# 11_Clock_1.net
KiCad netlist of a schematic drawn in Altium Designer
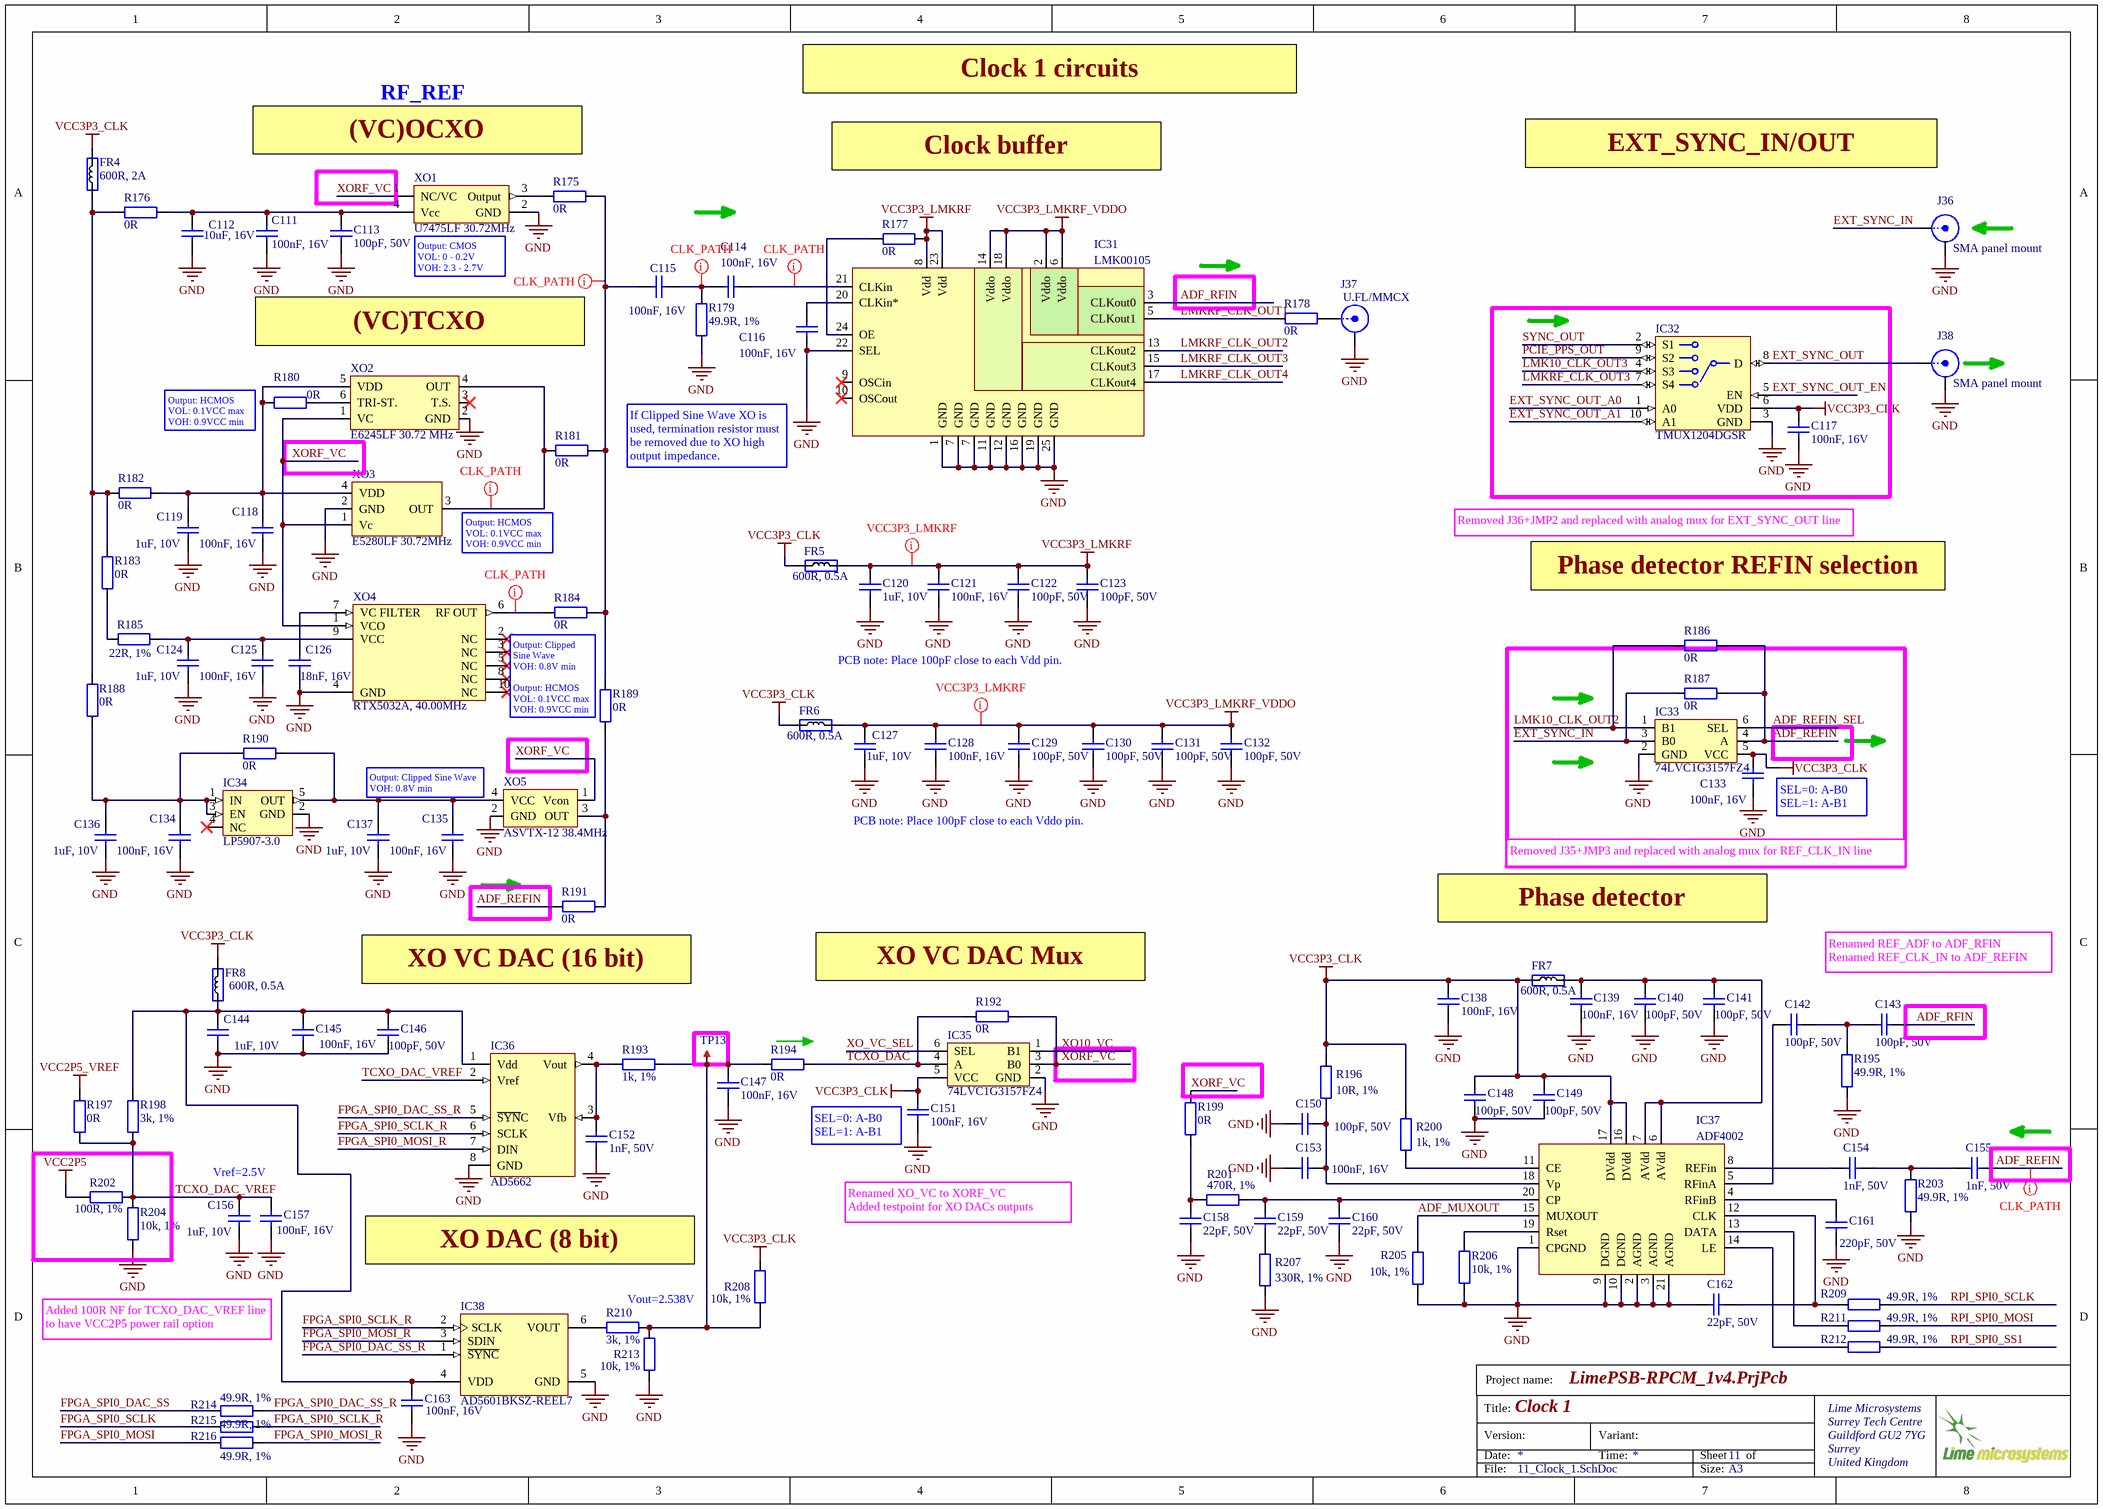
[diagram p0: 11_Clock_1.SchDoc]

(export (version "E")
  (design (tool "Eeschema 10.0.6"))
  (components
    (comp (ref "C111")
      (value "100nF, 16V")
      (footprint "CAP0402")
      (fields
        (field (name "MANUFACTURER") "Murata Electronics")
        (field (name "TOLERANCE") "10 %")
        (field (name "MANUFACTURER PART NUMBER") "GRM155R71C104KA88D")
      )
      (libsource (lib "LimeMicroAltiumLib_schLib") (part "Cap_0402"))
    )
    (comp (ref "C112")
      (value "10uF, 16V")
      (footprint "CAP0603")
      (fields (field (name "MANUFACTURER") "Yageo") (field (name "TOLERANCE") "±20%"))
      (libsource (lib "LimeMicroAltiumLib_schLib") (part "Cap_0603"))
    )
    (comp (ref "C113")
      (value "100pF, 50V")
      (footprint "CAP0402")
      (fields (field (name "TOLERANCE") "±5%") (field (name "MANUFACTURER") "Yageo"))
      (libsource (lib "LimeMicroAltiumLib_schLib") (part "Cap_0402"))
    )
    (comp (ref "C114")
      (value "100nF, 16V")
      (footprint "CAP0402")
      (fields
        (field (name "MANUFACTURER") "Murata Electronics")
        (field (name "TOLERANCE") "10 %")
        (field (name "MANUFACTURER PART NUMBER") "GRM155R71C104KA88D")
      )
      (libsource (lib "LimeMicroAltiumLib_schLib") (part "Cap_0402"))
    )
    (comp (ref "C115")
      (value "100nF, 16V")
      (footprint "CAP0402")
      (fields
        (field (name "MANUFACTURER") "Murata Electronics")
        (field (name "TOLERANCE") "10 %")
        (field (name "MANUFACTURER PART NUMBER") "GRM155R71C104KA88D")
      )
      (libsource (lib "LimeMicroAltiumLib_schLib") (part "Cap_0402"))
    )
    (comp (ref "C116")
      (value "100nF, 16V")
      (footprint "CAP0402")
      (fields
        (field (name "MANUFACTURER") "Murata Electronics")
        (field (name "TOLERANCE") "10 %")
        (field (name "MANUFACTURER PART NUMBER") "GRM155R71C104KA88D")
      )
      (libsource (lib "LimeMicroAltiumLib_schLib") (part "Cap_0402"))
    )
    (comp (ref "C117")
      (value "100nF, 16V")
      (footprint "CAP0402")
      (fields
        (field (name "MANUFACTURER") "Murata Electronics")
        (field (name "TOLERANCE") "10 %")
        (field (name "MANUFACTURER PART NUMBER") "GRM155R71C104KA88D")
      )
      (libsource (lib "LimeMicroAltiumLib_schLib") (part "Cap_0402"))
    )
    (comp (ref "C118")
      (value "100nF, 16V")
      (footprint "CAP0402")
      (fields
        (field (name "MANUFACTURER") "Murata Electronics")
        (field (name "TOLERANCE") "10 %")
        (field (name "MANUFACTURER PART NUMBER") "GRM155R71C104KA88D")
      )
      (libsource (lib "LimeMicroAltiumLib_schLib") (part "Cap_0402"))
    )
    (comp (ref "C119")
      (value "1uF, 10V")
      (footprint "CAP0402")
      (description "CAP CER 1UF 10V X5R 0402")
      (fields (field (name "MANUFACTURER") "Yageo"))
      (libsource (lib "LimeMicroAltiumLib_schLib") (part "Cap_0402"))
    )
    (comp (ref "C120")
      (value "1uF, 10V")
      (footprint "CAP0402")
      (description "CAP CER 1UF 10V X5R 0402")
      (fields (field (name "MANUFACTURER") "Yageo") (field (name "TOLERANCE") "±20%"))
      (libsource (lib "LimeMicroAltiumLib_schLib") (part "Cap_0402"))
    )
    (comp (ref "C121")
      (value "100nF, 16V")
      (footprint "CAP0402")
      (fields
        (field (name "MANUFACTURER") "Murata Electronics")
        (field (name "TOLERANCE") "10 %")
        (field (name "MANUFACTURER PART NUMBER") "GRM155R71C104KA88D")
      )
      (libsource (lib "LimeMicroAltiumLib_schLib") (part "Cap_0402"))
    )
    (comp (ref "C122")
      (value "100pF, 50V")
      (footprint "CAP0402")
      (fields (field (name "MANUFACTURER") "Yageo") (field (name "TOLERANCE") "±5%"))
      (libsource (lib "LimeMicroAltiumLib_schLib") (part "Cap_0402"))
    )
    (comp (ref "C123")
      (value "100pF, 50V")
      (footprint "CAP0402")
      (fields (field (name "MANUFACTURER") "Yageo") (field (name "TOLERANCE") "±5%"))
      (libsource (lib "LimeMicroAltiumLib_schLib") (part "Cap_0402"))
    )
    (comp (ref "C124")
      (value "1uF, 10V")
      (footprint "CAP0402")
      (description "CAP CER 1UF 10V X5R 0402")
      (fields (field (name "MANUFACTURER") "Yageo"))
      (libsource (lib "LimeMicroAltiumLib_schLib") (part "Cap_0402"))
    )
    (comp (ref "C125")
      (value "100nF, 16V")
      (footprint "CAP0402")
      (fields
        (field (name "MANUFACTURER") "Murata Electronics")
        (field (name "TOLERANCE") "10 %")
        (field (name "MANUFACTURER PART NUMBER") "GRM155R71C104KA88D")
      )
      (libsource (lib "LimeMicroAltiumLib_schLib") (part "Cap_0402"))
    )
    (comp (ref "C126")
      (value "18nF, 16V")
      (footprint "CAP0402")
      (fields (field (name "MANUFACTURER") "Yageo") (field (name "TOLERANCE") "±10%"))
      (libsource (lib "LimeMicroAltiumLib_schLib") (part "Cap_0402"))
    )
    (comp (ref "C127")
      (value "1uF, 10V")
      (footprint "CAP0402")
      (description "CAP CER 1UF 10V X5R 0402")
      (fields (field (name "MANUFACTURER") "Yageo") (field (name "TOLERANCE") "±20%"))
      (libsource (lib "LimeMicroAltiumLib_schLib") (part "Cap_0402"))
    )
    (comp (ref "C128")
      (value "100nF, 16V")
      (footprint "CAP0402")
      (fields
        (field (name "MANUFACTURER") "Murata Electronics")
        (field (name "TOLERANCE") "10 %")
        (field (name "MANUFACTURER PART NUMBER") "GRM155R71C104KA88D")
      )
      (libsource (lib "LimeMicroAltiumLib_schLib") (part "Cap_0402"))
    )
    (comp (ref "C129")
      (value "100pF, 50V")
      (footprint "CAP0402")
      (fields (field (name "MANUFACTURER") "Yageo") (field (name "TOLERANCE") "±5%"))
      (libsource (lib "LimeMicroAltiumLib_schLib") (part "Cap_0402"))
    )
    (comp (ref "C130")
      (value "100pF, 50V")
      (footprint "CAP0402")
      (fields (field (name "MANUFACTURER") "Yageo") (field (name "TOLERANCE") "±5%"))
      (libsource (lib "LimeMicroAltiumLib_schLib") (part "Cap_0402"))
    )
    (comp (ref "C131")
      (value "100pF, 50V")
      (footprint "CAP0402")
      (fields (field (name "MANUFACTURER") "Yageo") (field (name "TOLERANCE") "±5%"))
      (libsource (lib "LimeMicroAltiumLib_schLib") (part "Cap_0402"))
    )
    (comp (ref "C132")
      (value "100pF, 50V")
      (footprint "CAP0402")
      (fields (field (name "MANUFACTURER") "Yageo") (field (name "TOLERANCE") "±5%"))
      (libsource (lib "LimeMicroAltiumLib_schLib") (part "Cap_0402"))
    )
    (comp (ref "C133")
      (value "100nF, 16V")
      (footprint "CAP0402")
      (fields
        (field (name "MANUFACTURER") "Murata Electronics")
        (field (name "TOLERANCE") "10 %")
        (field (name "MANUFACTURER PART NUMBER") "GRM155R71C104KA88D")
      )
      (libsource (lib "LimeMicroAltiumLib_schLib") (part "Cap_0402"))
    )
    (comp (ref "C134")
      (value "100nF, 16V")
      (footprint "CAP0402")
      (fields
        (field (name "MANUFACTURER") "Murata Electronics")
        (field (name "TOLERANCE") "10 %")
        (field (name "MANUFACTURER PART NUMBER") "GRM155R71C104KA88D")
      )
      (libsource (lib "") (part "Cap_0402_1"))
    )
    (comp (ref "C135")
      (value "100nF, 16V")
      (footprint "CAP0402")
      (fields
        (field (name "MANUFACTURER") "Murata Electronics")
        (field (name "TOLERANCE") "10 %")
        (field (name "MANUFACTURER PART NUMBER") "GRM155R71C104KA88D")
      )
      (libsource (lib "") (part "Cap_0402_1"))
    )
    (comp (ref "C136")
      (value "1uF, 10V")
      (footprint "CAP0402")
      (fields (field (name "MANUFACTURER") "Yageo"))
      (libsource (lib "") (part "Cap_0402_1"))
    )
    (comp (ref "C137")
      (value "1uF, 10V")
      (footprint "CAP0402")
      (fields (field (name "MANUFACTURER") "Yageo"))
      (libsource (lib "") (part "Cap_0402_1"))
    )
    (comp (ref "C138")
      (value "100nF, 16V")
      (footprint "CAP0402")
      (fields
        (field (name "MANUFACTURER") "Murata Electronics")
        (field (name "TOLERANCE") "10 %")
        (field (name "MANUFACTURER PART NUMBER") "GRM155R71C104KA88D")
      )
      (libsource (lib "LimeMicroAltiumLib_schLib") (part "Cap_0402"))
    )
    (comp (ref "C139")
      (value "100nF, 16V")
      (footprint "CAP0402")
      (fields
        (field (name "MANUFACTURER") "Murata Electronics")
        (field (name "TOLERANCE") "10 %")
        (field (name "MANUFACTURER PART NUMBER") "GRM155R71C104KA88D")
      )
      (libsource (lib "LimeMicroAltiumLib_schLib") (part "Cap_0402"))
    )
    (comp (ref "C140")
      (value "100pF, 50V")
      (footprint "CAP0402")
      (fields (field (name "MANUFACTURER") "Yageo") (field (name "TOLERANCE") "±5%"))
      (libsource (lib "LimeMicroAltiumLib_schLib") (part "Cap_0402"))
    )
    (comp (ref "C141")
      (value "100pF, 50V")
      (footprint "CAP0402")
      (fields (field (name "MANUFACTURER") "Yageo") (field (name "TOLERANCE") "±5%"))
      (libsource (lib "LimeMicroAltiumLib_schLib") (part "Cap_0402"))
    )
    (comp (ref "C142")
      (value "100pF, 50V")
      (footprint "CAP0402")
      (fields (field (name "MANUFACTURER") "Yageo") (field (name "TOLERANCE") "±5%"))
      (libsource (lib "LimeMicroAltiumLib_schLib") (part "Cap_0402"))
    )
    (comp (ref "C143")
      (value "100pF, 50V")
      (footprint "CAP0402")
      (fields (field (name "MANUFACTURER") "Yageo") (field (name "TOLERANCE") "±5%"))
      (libsource (lib "LimeMicroAltiumLib_schLib") (part "Cap_0402"))
    )
    (comp (ref "C144")
      (value "1uF, 10V")
      (footprint "CAP0402")
      (description "CAP CER 1UF 10V X5R 0402")
      (fields (field (name "MANUFACTURER") "Yageo") (field (name "TOLERANCE") "±20%"))
      (libsource (lib "LimeMicroAltiumLib_schLib") (part "Cap_0402"))
    )
    (comp (ref "C145")
      (value "100nF, 16V")
      (footprint "CAP0402")
      (fields
        (field (name "TOLERANCE") "10 %")
        (field (name "MANUFACTURER") "Murata Electronics")
        (field (name "MANUFACTURER PART NUMBER") "GRM155R71C104KA88D")
      )
      (libsource (lib "LimeFPGAboard_schLib") (part "Cap_0603"))
    )
    (comp (ref "C146")
      (value "100pF, 50V")
      (footprint "CAP0402")
      (fields (field (name "MANUFACTURER") "Yageo") (field (name "TOLERANCE") "±5%"))
      (libsource (lib "LimeMicroAltiumLib_schLib") (part "Cap_0402"))
    )
    (comp (ref "C147")
      (value "100nF, 16V")
      (footprint "CAP0402")
      (fields
        (field (name "MANUFACTURER") "Murata Electronics")
        (field (name "TOLERANCE") "10 %")
        (field (name "MANUFACTURER PART NUMBER") "GRM155R71C104KA88D")
      )
      (libsource (lib "LimeMicroAltiumLib_schLib") (part "Cap_0402"))
    )
    (comp (ref "C148")
      (value "100pF, 50V")
      (footprint "CAP0402")
      (fields (field (name "MANUFACTURER") "Yageo") (field (name "TOLERANCE") "±5%"))
      (libsource (lib "LimeMicroAltiumLib_schLib") (part "Cap_0402"))
    )
    (comp (ref "C149")
      (value "100pF, 50V")
      (footprint "CAP0402")
      (fields (field (name "MANUFACTURER") "Yageo") (field (name "TOLERANCE") "±5%"))
      (libsource (lib "LimeMicroAltiumLib_schLib") (part "Cap_0402"))
    )
    (comp (ref "C150")
      (value "100pF, 50V")
      (footprint "CAP0402")
      (fields (field (name "MANUFACTURER") "Yageo") (field (name "TOLERANCE") "±5%"))
      (libsource (lib "LimeMicroAltiumLib_schLib") (part "Cap_0402"))
    )
    (comp (ref "C151")
      (value "100nF, 16V")
      (footprint "CAP0402")
      (fields
        (field (name "MANUFACTURER") "Murata Electronics")
        (field (name "TOLERANCE") "10 %")
        (field (name "MANUFACTURER PART NUMBER") "GRM155R71C104KA88D")
      )
      (libsource (lib "LimeMicroAltiumLib_schLib") (part "Cap_0402"))
    )
    (comp (ref "C152")
      (value "1nF, 50V")
      (footprint "CAP0402")
      (fields
        (field (name "TOLERANCE") "±10%")
        (field (name "MANUFACTURER") "Murata Electronics North America")
      )
      (libsource (lib "LimeMicroAltiumLib_schLib") (part "Cap_0402"))
    )
    (comp (ref "C153")
      (value "100nF, 16V")
      (footprint "CAP0402")
      (fields
        (field (name "MANUFACTURER") "Murata Electronics")
        (field (name "TOLERANCE") "10 %")
        (field (name "MANUFACTURER PART NUMBER") "GRM155R71C104KA88D")
      )
      (libsource (lib "LimeMicroAltiumLib_schLib") (part "Cap_0402"))
    )
    (comp (ref "C154")
      (value "1nF, 50V")
      (footprint "CAP0402")
      (fields
        (field (name "TOLERANCE") "±10%")
        (field (name "MANUFACTURER") "Murata Electronics North America")
      )
      (libsource (lib "LimeMicroAltiumLib_schLib") (part "Cap_0402"))
    )
    (comp (ref "C155")
      (value "1nF, 50V")
      (footprint "CAP0402")
      (fields
        (field (name "TOLERANCE") "±10%")
        (field (name "MANUFACTURER") "Murata Electronics North America")
      )
      (libsource (lib "LimeMicroAltiumLib_schLib") (part "Cap_0402"))
    )
    (comp (ref "C156")
      (value "1uF, 10V")
      (footprint "CAP0402")
      (description "CAP CER 1UF 10V X5R 0402")
      (fields (field (name "MANUFACTURER") "Yageo") (field (name "TOLERANCE") "±20%"))
      (libsource (lib "LimeMicroAltiumLib_schLib") (part "Cap_0402"))
    )
    (comp (ref "C157")
      (value "100nF, 16V")
      (footprint "CAP0402")
      (fields
        (field (name "TOLERANCE") "10 %")
        (field (name "MANUFACTURER") "Murata Electronics")
        (field (name "MANUFACTURER PART NUMBER") "GRM155R71C104KA88D")
      )
      (libsource (lib "LimeFPGAboard_schLib") (part "Cap_0603"))
    )
    (comp (ref "C158")
      (value "22pF, 50V")
      (footprint "CAP0402")
      (fields (field (name "TOLERANCE") "±5%") (field (name "MANUFACTURER") "Yageo"))
      (libsource (lib "LimeMicroAltiumLib_schLib") (part "Cap_0402"))
    )
    (comp (ref "C159")
      (value "22pF, 50V")
      (footprint "CAP0402")
      (fields (field (name "TOLERANCE") "±5%") (field (name "MANUFACTURER") "Yageo"))
      (libsource (lib "LimeMicroAltiumLib_schLib") (part "Cap_0402"))
    )
    (comp (ref "C160")
      (value "22pF, 50V")
      (footprint "CAP0402")
      (fields (field (name "TOLERANCE") "±5%") (field (name "MANUFACTURER") "Yageo"))
      (libsource (lib "LimeMicroAltiumLib_schLib") (part "Cap_0402"))
    )
    (comp (ref "C161")
      (value "220pF, 50V")
      (footprint "CAP0402")
      (fields (field (name "MANUFACTURER") "Yageo") (field (name "TOLERANCE") "±10%"))
      (libsource (lib "LimeMicroAltiumLib_schLib") (part "Cap_0402"))
    )
    (comp (ref "C162")
      (value "22pF, 50V")
      (footprint "CAP0402")
      (fields (field (name "TOLERANCE") "±5%") (field (name "MANUFACTURER") "Yageo"))
      (libsource (lib "LimeMicroAltiumLib_schLib") (part "Cap_0402"))
    )
    (comp (ref "C163")
      (value "100nF, 16V")
      (footprint "CAP0402")
      (fields
        (field (name "TOLERANCE") "10 %")
        (field (name "MANUFACTURER") "Murata Electronics")
        (field (name "MANUFACTURER PART NUMBER") "GRM155R71C104KA88D")
      )
      (libsource (lib "LimeFPGAboard_schLib") (part "Cap_0603"))
    )
    (comp (ref "FR4")
      (value "600R, 2A")
      (footprint "RES0805")
      (fields (field (name "MANUFACTURER") "TDK Corporation"))
      (libsource (lib "LimeFPGAboard_schLib") (part "Ferrite"))
    )
    (comp (ref "FR5")
      (value "600R, 0.5A")
      (footprint "RES0402")
      (fields (field (name "MANUFACTURER") "Murata") (field (name "TOLERANCE") "25%"))
      (libsource (lib "LimeMicroAltiumLib_schLib") (part "Ferrite"))
    )
    (comp (ref "FR6")
      (value "600R, 0.5A")
      (footprint "RES0402")
      (fields (field (name "MANUFACTURER") "Murata") (field (name "TOLERANCE") "25%"))
      (libsource (lib "LimeMicroAltiumLib_schLib") (part "Ferrite"))
    )
    (comp (ref "FR7")
      (value "600R, 0.5A")
      (footprint "RES0402")
      (fields (field (name "MANUFACTURER") "Murata") (field (name "TOLERANCE") "25%"))
      (libsource (lib "LimeMicroAltiumLib_schLib") (part "Ferrite"))
    )
    (comp (ref "FR8")
      (value "600R, 0.5A")
      (footprint "RES0402")
      (fields (field (name "MANUFACTURER") "Murata") (field (name "TOLERANCE") "25%"))
      (libsource (lib "LimeMicroAltiumLib_schLib") (part "Ferrite"))
    )
    (comp (ref "IC31")
      (value "LMK00105")
      (footprint "LMK00105SQ")
      (fields (field (name "MANUFACTURER") "Texas Instruments"))
      (libsource (lib "LimeMicroAltiumLib_schLib") (part "LMK00105"))
    )
    (comp (ref "IC32")
      (value "TMUX1204DGSR")
      (footprint "TMUX1204DGSR_ANALOG_SWITCH_10-TSSOP")
      (fields (field (name "MANUFACTURER") "Texas Instruments"))
      (libsource (lib "LimeMicroAltiumLib") (part "TMUX1204DGSR_ANALOG_SWITCH"))
    )
    (comp (ref "IC33")
      (value "74LVC1G3157FZ4")
      (footprint "74LVC1G3157FZ4_SPDT_SW_DFN1410-6")
      (fields (field (name "MANUFACTURER") "Diodes"))
      (libsource (lib "") (part "74LVC1G3157FZ4_SPDT_SW_1"))
    )
    (comp (ref "IC34")
      (value "LP5907-3.0")
      (footprint "SOT23-5")
      (fields (field (name "MANUFACTURER") "Texas Instruments"))
      (libsource (lib "LimeMicroAltiumLib_schLib_r01") (part "LP5907"))
    )
    (comp (ref "IC35")
      (value "74LVC1G3157FZ4")
      (footprint "74LVC1G3157FZ4_SPDT_SW_DFN1410-6")
      (fields (field (name "MANUFACTURER") "Diodes"))
      (libsource (lib "LimeMicroAltiumLib_schLib_r04") (part "74LVC1G3157FZ4_SPDT_SW"))
    )
    (comp (ref "IC36")
      (value "AD5662")
      (footprint "AD5662_SOT23-8")
      (fields (field (name "MANUFACTURER") "Analog Devices Inc."))
      (libsource (lib "LimeMicroAltiumLib_schLib") (part "AD5662"))
    )
    (comp (ref "IC37")
      (value "ADF4002")
      (footprint "ADF4002")
      (fields (field (name "MANUFACTURER") "Analog Devices Inc"))
      (libsource (lib "LimeMicroAltiumLib_schLib") (part "ADF4002"))
    )
    (comp (ref "IC38")
      (value "AD5601BKSZ-REEL7")
      (footprint "AD5601_SOT23-6")
      (fields (field (name "GENERIC PART NUMBER") "AD5601") (field (name "MANUFACTURER") "Analog Devices"))
      (libsource (lib "LimeMicroAltiumLib_schLib") (part "AD5601BKSZ-REEL7"))
    )
    (comp (ref "J36")
      (value "SMA panel mount")
      (footprint "SMA_connector_side")
      (description "CONN SMA JACK STR 50OHM EDGE MNT")
      (fields (field (name "MANUFACTURER") "Linx"))
      (libsource (lib "") (part "RF_IF_connector_1"))
    )
    (comp (ref "J37")
      (value "U.FL/MMCX")
      (footprint "MMCX_UFL_conn_u")
      (description "CONN UMC RCPT STR 50 OHM SMD")
      (fields (field (name "MANUFACTURER") "Molex, LLC"))
      (libsource (lib "LimeMicroAltiumLib_schLib") (part "RF_IF_connector"))
    )
    (comp (ref "J38")
      (value "SMA panel mount")
      (footprint "SMA_connector_side")
      (description "CONN SMA JACK STR 50OHM EDGE MNT")
      (fields (field (name "MANUFACTURER") "Linx"))
      (libsource (lib "") (part "RF_IF_connector_1"))
    )
    (comp (ref "R175")
      (value "0R")
      (footprint "RES0402_v2")
      (fields (field (name "MANUFACTURER") "Yageo") (field (name "TOLERANCE") "Jumper"))
      (libsource (lib "LimeMicroAltiumLib_schLib") (part "Res_0402"))
    )
    (comp (ref "R176")
      (value "0R")
      (footprint "RES0402")
      (fields (field (name "MANUFACTURER") "Yageo") (field (name "TOLERANCE") "Jumper"))
      (libsource (lib "LimeMicroAltiumLib_schLib") (part "Res_0402"))
    )
    (comp (ref "R177")
      (value "0R")
      (footprint "RES0402")
      (fields (field (name "MANUFACTURER") "Yageo") (field (name "TOLERANCE") "Jumper"))
      (libsource (lib "LimeMicroAltiumLib_schLib") (part "Res_0402"))
    )
    (comp (ref "R178")
      (value "0R")
      (footprint "RES0402")
      (fields (field (name "MANUFACTURER") "Yageo") (field (name "TOLERANCE") "Jumper"))
      (libsource (lib "") (part "Res_0402_1"))
    )
    (comp (ref "R179")
      (value "49.9R, 1%")
      (footprint "RES0402")
      (fields
        (field (name "TOLERANCE") "±1%")
        (field (name "MANUFACTURER") "Samsung Electro-Mechanics America, Inc.")
      )
      (libsource (lib "LimeMicroAltiumLib_schLib") (part "Res_0402"))
    )
    (comp (ref "R180")
      (value "0R")
      (footprint "RES0402")
      (fields (field (name "MANUFACTURER") "Yageo") (field (name "TOLERANCE") "Jumper"))
      (libsource (lib "LimeMicroAltiumLib_schLib") (part "Res_0402"))
    )
    (comp (ref "R181")
      (value "0R")
      (footprint "RES0402_v2")
      (fields (field (name "MANUFACTURER") "Yageo") (field (name "TOLERANCE") "Jumper"))
      (libsource (lib "LimeMicroAltiumLib_schLib") (part "Res_0402"))
    )
    (comp (ref "R182")
      (value "0R")
      (footprint "RES0402")
      (fields (field (name "MANUFACTURER") "Yageo") (field (name "TOLERANCE") "Jumper"))
      (libsource (lib "LimeMicroAltiumLib_schLib") (part "Res_0402"))
    )
    (comp (ref "R183")
      (value "0R")
      (footprint "RES0402")
      (fields (field (name "MANUFACTURER") "Yageo") (field (name "TOLERANCE") "Jumper"))
      (libsource (lib "LimeMicroAltiumLib_schLib") (part "Res_0402"))
    )
    (comp (ref "R184")
      (value "0R")
      (footprint "RES0402_v2")
      (fields (field (name "MANUFACTURER") "Yageo") (field (name "TOLERANCE") "Jumper"))
      (libsource (lib "LimeMicroAltiumLib_schLib") (part "Res_0402"))
    )
    (comp (ref "R185")
      (value "22R, 1%")
      (footprint "RES0402")
      (fields (field (name "TOLERANCE") "±1%") (field (name "MANUFACTURER") "Yageo"))
      (libsource (lib "LimeFPGAboard_schLib") (part "Res_0402"))
    )
    (comp (ref "R186")
      (value "0R")
      (footprint "RES0402_v2")
      (fields (field (name "MANUFACTURER") "Yageo") (field (name "TOLERANCE") "Jumper"))
      (libsource (lib "LimeMicroAltiumLib_schLib") (part "Res_0402"))
    )
    (comp (ref "R187")
      (value "0R")
      (footprint "RES0402_v2")
      (fields (field (name "MANUFACTURER") "Yageo") (field (name "TOLERANCE") "Jumper"))
      (libsource (lib "LimeMicroAltiumLib_schLib") (part "Res_0402"))
    )
    (comp (ref "R188")
      (value "0R")
      (footprint "RES0402")
      (fields (field (name "MANUFACTURER") "Yageo") (field (name "TOLERANCE") "Jumper"))
      (libsource (lib "") (part "Res_0402_1"))
    )
    (comp (ref "R189")
      (value "0R")
      (footprint "RES0402_v2")
      (fields (field (name "MANUFACTURER") "Yageo") (field (name "TOLERANCE") "Jumper"))
      (libsource (lib "") (part "Res_0402_1"))
    )
    (comp (ref "R190")
      (value "0R")
      (footprint "RES0402")
      (fields (field (name "MANUFACTURER") "Yageo") (field (name "TOLERANCE") "Jumper"))
      (libsource (lib "") (part "Res_0402_1"))
    )
    (comp (ref "R191")
      (value "0R")
      (footprint "RES0402_v2")
      (fields (field (name "MANUFACTURER") "Yageo") (field (name "TOLERANCE") "Jumper"))
      (libsource (lib "LimeMicroAltiumLib_schLib") (part "Res_0402"))
    )
    (comp (ref "R192")
      (value "0R")
      (footprint "RES0402_v2")
      (fields (field (name "MANUFACTURER") "Yageo") (field (name "TOLERANCE") "Jumper"))
      (libsource (lib "LimeMicroAltiumLib_schLib") (part "Res_0402"))
    )
    (comp (ref "R193")
      (value "1k, 1%")
      (footprint "RES0402")
      (fields (field (name "MANUFACTURER") "Stackpole Electronics Inc") (field (name "TOLERANCE") "±1%"))
      (libsource (lib "LimeMicroAltiumLib_schLib") (part "Res_0402"))
    )
    (comp (ref "R194")
      (value "0R")
      (footprint "RES0402")
      (fields (field (name "MANUFACTURER") "Yageo") (field (name "TOLERANCE") "Jumper"))
      (libsource (lib "LimeMicroAltiumLib_schLib") (part "Res_0402"))
    )
    (comp (ref "R195")
      (value "49.9R, 1%")
      (footprint "RES0402")
      (fields
        (field (name "TOLERANCE") "±1%")
        (field (name "MANUFACTURER") "Samsung Electro-Mechanics America, Inc.")
      )
      (libsource (lib "LimeMicroAltiumLib_schLib") (part "Res_0402"))
    )
    (comp (ref "R196")
      (value "10R, 1%")
      (footprint "RES0402")
      (fields (field (name "MANUFACTURER") "Stackpole Electronics") (field (name "TOLERANCE") "1%"))
      (libsource (lib "LimeMicroAltiumLib_schLib") (part "Res_0402"))
    )
    (comp (ref "R197")
      (value "0R")
      (footprint "RES0402_v2")
      (fields (field (name "MANUFACTURER") "Yageo") (field (name "TOLERANCE") "Jumper"))
      (libsource (lib "LimeMicroAltiumLib_schLib") (part "Res_0402"))
    )
    (comp (ref "R198")
      (value "3k, 1%")
      (footprint "RES0402")
      (fields (field (name "TOLERANCE") "±1%") (field (name "MANUFACTURER") "Vishay Dale"))
      (libsource (lib "LimeMicroAltiumLib_schLib") (part "Res_0402"))
    )
    (comp (ref "R199")
      (value "0R")
      (footprint "RES0402")
      (fields (field (name "MANUFACTURER") "Yageo") (field (name "TOLERANCE") "Jumper"))
      (libsource (lib "LimeMicroAltiumLib_schLib") (part "Res_0402"))
    )
    (comp (ref "R200")
      (value "1k, 1%")
      (footprint "RES0402")
      (fields (field (name "MANUFACTURER") "Stackpole Electronics Inc") (field (name "TOLERANCE") "±1%"))
      (libsource (lib "LimeMicroAltiumLib_schLib") (part "Res_0402"))
    )
    (comp (ref "R201")
      (value "470R, 1%")
      (footprint "RES0402")
      (fields (field (name "TOLERANCE") "1%") (field (name "MANUFACTURER") "Yageo"))
      (libsource (lib "") (part "Res_0402_1"))
    )
    (comp (ref "R202")
      (value "100R, 1%")
      (footprint "RES0402")
      (fields (field (name "TOLERANCE") "±1%") (field (name "MANUFACTURER") "Stackpole Electronics Inc."))
      (libsource (lib "LimeMicroAltiumLib_schLib") (part "Res_0402"))
    )
    (comp (ref "R203")
      (value "49.9R, 1%")
      (footprint "RES0402")
      (fields
        (field (name "TOLERANCE") "±1%")
        (field (name "MANUFACTURER") "Samsung Electro-Mechanics America, Inc.")
      )
      (libsource (lib "LimeMicroAltiumLib_schLib") (part "Res_0402"))
    )
    (comp (ref "R204")
      (value "10k, 1%")
      (footprint "RES0402")
      (fields (field (name "MANUFACTURER") "Yageo") (field (name "TOLERANCE") "±1%"))
      (libsource (lib "LimeMicroAltiumLib_schLib") (part "Res_0402"))
    )
    (comp (ref "R205")
      (value "10k, 1%")
      (footprint "RES0402")
      (fields (field (name "MANUFACTURER") "Yageo") (field (name "TOLERANCE") "±1%"))
      (libsource (lib "LimeMicroAltiumLib_schLib") (part "Res_0402"))
    )
    (comp (ref "R206")
      (value "10k, 1%")
      (footprint "RES0402")
      (fields (field (name "MANUFACTURER") "Yageo") (field (name "TOLERANCE") "±1%"))
      (libsource (lib "LimeMicroAltiumLib_schLib") (part "Res_0402"))
    )
    (comp (ref "R207")
      (value "330R, 1%")
      (footprint "RES0402")
      (fields (field (name "MANUFACTURER") "Yageo") (field (name "TOLERANCE") "1%"))
      (libsource (lib "LimeMicroAltiumLib_schLib") (part "Res_0402"))
    )
    (comp (ref "R208")
      (value "10k, 1%")
      (footprint "RES0402")
      (fields (field (name "MANUFACTURER") "Yageo") (field (name "TOLERANCE") "±1%"))
      (libsource (lib "LimeMicroAltiumLib_schLib") (part "Res_0402"))
    )
    (comp (ref "R209")
      (value "49.9R, 1%")
      (footprint "RES0402")
      (fields
        (field (name "TOLERANCE") "±1%")
        (field (name "MANUFACTURER") "Samsung Electro-Mechanics America, Inc.")
      )
      (libsource (lib "LimeMicroAltiumLib_schLib") (part "Res_0402"))
    )
    (comp (ref "R210")
      (value "3k, 1%")
      (footprint "RES0402")
      (fields (field (name "TOLERANCE") "±1%") (field (name "MANUFACTURER") "Vishay Dale"))
      (libsource (lib "LimeMicroAltiumLib_schLib") (part "Res_0402"))
    )
    (comp (ref "R211")
      (value "49.9R, 1%")
      (footprint "RES0402")
      (fields
        (field (name "TOLERANCE") "±1%")
        (field (name "MANUFACTURER") "Samsung Electro-Mechanics America, Inc.")
      )
      (libsource (lib "LimeMicroAltiumLib_schLib") (part "Res_0402"))
    )
    (comp (ref "R212")
      (value "49.9R, 1%")
      (footprint "RES0402")
      (fields
        (field (name "TOLERANCE") "±1%")
        (field (name "MANUFACTURER") "Samsung Electro-Mechanics America, Inc.")
      )
      (libsource (lib "LimeMicroAltiumLib_schLib") (part "Res_0402"))
    )
    (comp (ref "R213")
      (value "10k, 1%")
      (footprint "RES0402")
      (fields (field (name "MANUFACTURER") "Yageo") (field (name "TOLERANCE") "±1%"))
      (libsource (lib "LimeMicroAltiumLib_schLib") (part "Res_0402"))
    )
    (comp (ref "R214")
      (value "49.9R, 1%")
      (footprint "RES0402")
      (fields
        (field (name "TOLERANCE") "±1%")
        (field (name "MANUFACTURER") "Samsung Electro-Mechanics America, Inc.")
      )
      (libsource (lib "LimeMicroAltiumLib_schLib") (part "Res_0402"))
    )
    (comp (ref "R215")
      (value "49.9R, 1%")
      (footprint "RES0402")
      (fields
        (field (name "TOLERANCE") "±1%")
        (field (name "MANUFACTURER") "Samsung Electro-Mechanics America, Inc.")
      )
      (libsource (lib "LimeMicroAltiumLib_schLib") (part "Res_0402"))
    )
    (comp (ref "R216")
      (value "49.9R, 1%")
      (footprint "RES0402")
      (fields
        (field (name "TOLERANCE") "±1%")
        (field (name "MANUFACTURER") "Samsung Electro-Mechanics America, Inc.")
      )
      (libsource (lib "LimeMicroAltiumLib_schLib") (part "Res_0402"))
    )
    (comp (ref "TP13")
      (value "TESTPOINT_PAD")
      (footprint "TP_PAD_1p5MM")
      (description "Test Point PCB mount Miniature White")
      (libsource (lib "LimeMicroAltiumLib_schLib_r04") (part "TESTPOINT_PAD"))
    )
    (comp (ref "XO1")
      (value "U7475LF 30.72MHz")
      (footprint "AOCJYR-10.000MHz")
      (fields (field (name "MANUFACTURER") "Rakon"))
      (libsource (lib "LimeMicroAltiumLib_schLib") (part "AOCJYR-10.000MHz"))
    )
    (comp (ref "XO2")
      (value "E6245LF 30.72 MHz")
      (footprint "RAKON_RPT7050A")
      (fields (field (name "MANUFACTURER") "Rakon"))
      (libsource (lib "LimeMicroAltiumLib_schLib") (part "RPT7050A"))
    )
    (comp (ref "XO3")
      (value "E5280LF 30.72MHz")
      (footprint "RAKON_TXCO")
      (fields (field (name "MANUFACTURER") "Rakon"))
      (libsource (lib "LimeMicroAltiumLib_schLib") (part "TXCO"))
    )
    (comp (ref "XO4")
      (value "RTX5032A, 40.00MHz")
      (footprint "RAKON_RTX5032A")
      (fields (field (name "MANUFACTURER") "Rakon"))
      (libsource (lib "LimeMicroAltiumLib_schLib") (part "Rakon_RTX5032A"))
    )
    (comp (ref "XO5")
      (value "ASVTX-12 38.4MHz")
      (footprint "CRYSTAL_4-LCC_2P5x2P0")
      (description "Oscillator Crystal")
      (fields (field (name "MANUFACTURER") "Abracon"))
      (libsource (lib "LimeMicroAltiumLib_schLib_r01") (part "ASVTX-12-A-38.400MHZ-H10-T_CRYSTAL"))
    )
  )
  (nets
    (net (code "2") (name "/ADF_MUXOUT") (class "Default")
      (node (ref "IC37") (pin "15") (pinfunction "MUXOUT_15") (pintype "passive"))
      (node (ref "R205") (pin "1") (pinfunction "1_1") (pintype "passive"))
    )
    (net (code "3") (name "/ADF_REFIN") (class "Default")
      (node (ref "C155") (pin "2") (pinfunction "2_2") (pintype "passive"))
      (node (ref "IC33") (pin "4") (pinfunction "A_4") (pintype "passive"))
      (node (ref "R186") (pin "1") (pinfunction "1_1") (pintype "passive"))
      (node (ref "R187") (pin "1") (pinfunction "1_1") (pintype "passive"))
      (node (ref "R191") (pin "2") (pinfunction "2_2") (pintype "passive"))
    )
    (net (code "4") (name "/ADF_REFIN_SEL") (class "Default")
      (node (ref "IC33") (pin "6") (pinfunction "SEL_6") (pintype "passive"))
    )
    (net (code "5") (name "/ADF_RFIN") (class "Default")
      (node (ref "C143") (pin "2") (pinfunction "2_2") (pintype "passive"))
      (node (ref "IC31") (pin "3") (pinfunction "CLKout0_3") (pintype "passive"))
    )
    (net (code "6") (name "/EXT_SYNC_IN") (class "Default")
      (node (ref "IC33") (pin "3") (pinfunction "B0_3") (pintype "passive"))
      (node (ref "J36") (pin "1") (pinfunction "X_1") (pintype "passive"))
      (node (ref "R187") (pin "2") (pinfunction "2_2") (pintype "passive"))
    )
    (net (code "7") (name "/EXT_SYNC_OUT") (class "Default")
      (node (ref "IC32") (pin "8") (pinfunction "D_8") (pintype "bidirectional"))
      (node (ref "J38") (pin "1") (pinfunction "X_1") (pintype "passive"))
    )
    (net (code "8") (name "/EXT_SYNC_OUT_A0") (class "Default")
      (node (ref "IC32") (pin "1") (pinfunction "A0_1") (pintype "input"))
    )
    (net (code "9") (name "/EXT_SYNC_OUT_A1") (class "Default")
      (node (ref "IC32") (pin "10") (pinfunction "A1_10") (pintype "bidirectional"))
    )
    (net (code "10") (name "/EXT_SYNC_OUT_EN") (class "Default")
      (node (ref "IC32") (pin "5") (pinfunction "EN_5") (pintype "input"))
    )
    (net (code "11") (name "/FPGA_SPI0_DAC_SS") (class "Default")
      (node (ref "R214") (pin "2") (pinfunction "2_2") (pintype "passive"))
    )
    (net (code "12") (name "/FPGA_SPI0_DAC_SS_R") (class "Default")
      (node (ref "IC36") (pin "5") (pinfunction "~{SYN}C_5") (pintype "input"))
      (node (ref "IC38") (pin "1") (pinfunction "~{SYNC}_1") (pintype "input"))
      (node (ref "R214") (pin "1") (pinfunction "1_1") (pintype "passive"))
    )
    (net (code "13") (name "/FPGA_SPI0_MOSI") (class "Default")
      (node (ref "R216") (pin "2") (pinfunction "2_2") (pintype "passive"))
    )
    (net (code "14") (name "/FPGA_SPI0_MOSI_R") (class "Default")
      (node (ref "IC36") (pin "7") (pinfunction "DIN_7") (pintype "input"))
      (node (ref "IC38") (pin "3") (pinfunction "SDIN_3") (pintype "input"))
      (node (ref "R216") (pin "1") (pinfunction "1_1") (pintype "passive"))
    )
    (net (code "15") (name "/FPGA_SPI0_SCLK") (class "Default")
      (node (ref "R215") (pin "2") (pinfunction "2_2") (pintype "passive"))
    )
    (net (code "16") (name "/FPGA_SPI0_SCLK_R") (class "Default")
      (node (ref "IC36") (pin "6") (pinfunction "SCLK_6") (pintype "input"))
      (node (ref "IC38") (pin "2") (pinfunction "SCLK_2") (pintype "input"))
      (node (ref "R215") (pin "1") (pinfunction "1_1") (pintype "passive"))
    )
    (net (code "17") (name "/LMK10_CLK_OUT2") (class "Default")
      (node (ref "IC33") (pin "1") (pinfunction "B1_1") (pintype "passive"))
      (node (ref "R186") (pin "2") (pinfunction "2_2") (pintype "passive"))
    )
    (net (code "18") (name "/LMK10_CLK_OUT3") (class "Default")
      (node (ref "IC32") (pin "4") (pinfunction "S3_4") (pintype "bidirectional"))
    )
    (net (code "19") (name "/LMKRF_CLK_OUT1") (class "Default")
      (node (ref "IC31") (pin "5") (pinfunction "CLKout1_5") (pintype "passive"))
      (node (ref "R178") (pin "2") (pinfunction "2_2") (pintype "passive"))
    )
    (net (code "20") (name "/LMKRF_CLK_OUT2") (class "Default")
      (node (ref "IC31") (pin "13") (pinfunction "CLKout2_13") (pintype "passive"))
    )
    (net (code "21") (name "/LMKRF_CLK_OUT3") (class "Default")
      (node (ref "IC31") (pin "15") (pinfunction "CLKout3_15") (pintype "passive"))
      (node (ref "IC32") (pin "7") (pinfunction "S4_7") (pintype "bidirectional"))
    )
    (net (code "22") (name "/LMKRF_CLK_OUT4") (class "Default")
      (node (ref "IC31") (pin "17") (pinfunction "CLKout4_17") (pintype "passive"))
    )
    (net (code "23") (name "/PCIE_PPS_OUT") (class "Default")
      (node (ref "IC32") (pin "9") (pinfunction "S2_9") (pintype "bidirectional"))
    )
    (net (code "24") (name "/RPI_SPI0_MOSI") (class "Default")
      (node (ref "R211") (pin "1") (pinfunction "1_1") (pintype "passive"))
    )
    (net (code "25") (name "/RPI_SPI0_SCLK") (class "Default")
      (node (ref "R209") (pin "1") (pinfunction "1_1") (pintype "passive"))
    )
    (net (code "26") (name "/RPI_SPI0_SS1") (class "Default")
      (node (ref "R212") (pin "1") (pinfunction "1_1") (pintype "passive"))
    )
    (net (code "27") (name "/SYNC_OUT") (class "Default")
      (node (ref "IC32") (pin "2") (pinfunction "S1_2") (pintype "bidirectional"))
    )
    (net (code "28") (name "/TCXO_DAC") (class "Default")
      (node (ref "IC35") (pin "4") (pinfunction "A_4") (pintype "passive"))
      (node (ref "R192") (pin "2") (pinfunction "2_2") (pintype "passive"))
      (node (ref "R194") (pin "1") (pinfunction "1_1") (pintype "passive"))
    )
    (net (code "29") (name "/TCXO_DAC_VREF") (class "Default")
      (node (ref "C156") (pin "2") (pinfunction "2_2") (pintype "passive"))
      (node (ref "C157") (pin "1") (pinfunction "1_1") (pintype "passive"))
      (node (ref "IC36") (pin "2") (pinfunction "Vref_2") (pintype "input"))
      (node (ref "R197") (pin "1") (pinfunction "1_1") (pintype "passive"))
      (node (ref "R198") (pin "1") (pinfunction "1_1") (pintype "passive"))
      (node (ref "R202") (pin "1") (pinfunction "1_1") (pintype "passive"))
      (node (ref "R204") (pin "1") (pinfunction "1_1") (pintype "passive"))
    )
    (net (code "30") (name "/XO10_VC") (class "Default")
      (node (ref "IC35") (pin "1") (pinfunction "B1_1") (pintype "passive"))
    )
    (net (code "31") (name "/XORF_VC") (class "Default")
      (node (ref "IC35") (pin "3") (pinfunction "B0_3") (pintype "passive"))
      (node (ref "R192") (pin "1") (pinfunction "1_1") (pintype "passive"))
      (node (ref "R199") (pin "2") (pinfunction "2_2") (pintype "passive"))
      (node (ref "XO1") (pin "1") (pinfunction "NC/VC_1") (pintype "passive"))
      (node (ref "XO2") (pin "1") (pinfunction "VC_1") (pintype "passive"))
      (node (ref "XO3") (pin "1") (pinfunction "Vc_1") (pintype "passive"))
      (node (ref "XO4") (pin "1") (pinfunction "VCO_1") (pintype "input"))
      (node (ref "XO5") (pin "1") (pinfunction "Vcon_1") (pintype "passive"))
    )
    (net (code "32") (name "/XO_VC_SEL") (class "Default")
      (node (ref "IC35") (pin "6") (pinfunction "SEL_6") (pintype "passive"))
    )
    (net (code "33") (name "GND") (class "Default")
      (node (ref "C111") (pin "1") (pinfunction "1_1") (pintype "passive"))
      (node (ref "C112") (pin "1") (pinfunction "1_1") (pintype "passive"))
      (node (ref "C113") (pin "2") (pinfunction "2_2") (pintype "passive"))
      (node (ref "C116") (pin "1") (pinfunction "1_1") (pintype "passive"))
      (node (ref "C117") (pin "1") (pinfunction "1_1") (pintype "passive"))
      (node (ref "C118") (pin "1") (pinfunction "1_1") (pintype "passive"))
      (node (ref "C119") (pin "1") (pinfunction "1_1") (pintype "passive"))
      (node (ref "C120") (pin "1") (pinfunction "1_1") (pintype "passive"))
      (node (ref "C121") (pin "1") (pinfunction "1_1") (pintype "passive"))
      (node (ref "C122") (pin "1") (pinfunction "1_1") (pintype "passive"))
      (node (ref "C123") (pin "1") (pinfunction "1_1") (pintype "passive"))
      (node (ref "C124") (pin "1") (pinfunction "1_1") (pintype "passive"))
      (node (ref "C125") (pin "1") (pinfunction "1_1") (pintype "passive"))
      (node (ref "C126") (pin "1") (pinfunction "1_1") (pintype "passive"))
      (node (ref "C127") (pin "1") (pinfunction "1_1") (pintype "passive"))
      (node (ref "C128") (pin "1") (pinfunction "1_1") (pintype "passive"))
      (node (ref "C129") (pin "1") (pinfunction "1_1") (pintype "passive"))
      (node (ref "C130") (pin "1") (pinfunction "1_1") (pintype "passive"))
      (node (ref "C131") (pin "1") (pinfunction "1_1") (pintype "passive"))
      (node (ref "C132") (pin "1") (pinfunction "1_1") (pintype "passive"))
      (node (ref "C133") (pin "1") (pinfunction "1_1") (pintype "passive"))
      (node (ref "C134") (pin "1") (pinfunction "1_1") (pintype "passive"))
      (node (ref "C135") (pin "1") (pinfunction "1_1") (pintype "passive"))
      (node (ref "C136") (pin "1") (pinfunction "1_1") (pintype "passive"))
      (node (ref "C137") (pin "1") (pinfunction "1_1") (pintype "passive"))
      (node (ref "C138") (pin "1") (pinfunction "1_1") (pintype "passive"))
      (node (ref "C139") (pin "1") (pinfunction "1_1") (pintype "passive"))
      (node (ref "C140") (pin "2") (pinfunction "2_2") (pintype "passive"))
      (node (ref "C141") (pin "2") (pinfunction "2_2") (pintype "passive"))
      (node (ref "C144") (pin "1") (pinfunction "1_1") (pintype "passive"))
      (node (ref "C145") (pin "2") (pinfunction "2_2") (pintype "passive"))
      (node (ref "C146") (pin "2") (pinfunction "2_2") (pintype "passive"))
      (node (ref "C147") (pin "1") (pinfunction "1_1") (pintype "passive"))
      (node (ref "C148") (pin "2") (pinfunction "2_2") (pintype "passive"))
      (node (ref "C149") (pin "2") (pinfunction "2_2") (pintype "passive"))
      (node (ref "C150") (pin "1") (pinfunction "1_1") (pintype "passive"))
      (node (ref "C151") (pin "1") (pinfunction "1_1") (pintype "passive"))
      (node (ref "C152") (pin "2") (pinfunction "2_2") (pintype "passive"))
      (node (ref "C153") (pin "2") (pinfunction "2_2") (pintype "passive"))
      (node (ref "C156") (pin "1") (pinfunction "1_1") (pintype "passive"))
      (node (ref "C157") (pin "2") (pinfunction "2_2") (pintype "passive"))
      (node (ref "C158") (pin "1") (pinfunction "1_1") (pintype "passive"))
      (node (ref "C160") (pin "1") (pinfunction "1_1") (pintype "passive"))
      (node (ref "C161") (pin "2") (pinfunction "2_2") (pintype "passive"))
      (node (ref "C162") (pin "2") (pinfunction "2_2") (pintype "passive"))
      (node (ref "C163") (pin "2") (pinfunction "2_2") (pintype "passive"))
      (node (ref "IC31") (pin "1") (pinfunction "GND_1") (pintype "passive"))
      (node (ref "IC31") (pin "11") (pinfunction "GND_11") (pintype "passive"))
      (node (ref "IC31") (pin "12") (pinfunction "GND_12") (pintype "passive"))
      (node (ref "IC31") (pin "16") (pinfunction "GND_16") (pintype "passive"))
      (node (ref "IC31") (pin "19") (pinfunction "GND_19") (pintype "passive"))
      (node (ref "IC31") (pin "22") (pinfunction "SEL_22") (pintype "passive"))
      (node (ref "IC31") (pin "25") (pinfunction "GND_25") (pintype "passive"))
      (node (ref "IC31") (pin "7") (pinfunction "GND_7") (pintype "passive"))
      (node (ref "IC32") (pin "3") (pinfunction "GND_3") (pintype "passive"))
      (node (ref "IC33") (pin "2") (pinfunction "GND_2") (pintype "passive"))
      (node (ref "IC34") (pin "2") (pinfunction "GND_2") (pintype "passive"))
      (node (ref "IC35") (pin "2") (pinfunction "GND_2") (pintype "passive"))
      (node (ref "IC36") (pin "8") (pinfunction "GND_8") (pintype "passive"))
      (node (ref "IC37") (pin "1") (pinfunction "CPGND_1") (pintype "passive"))
      (node (ref "IC37") (pin "10") (pinfunction "DGND_10") (pintype "passive"))
      (node (ref "IC37") (pin "2") (pinfunction "AGND_2") (pintype "passive"))
      (node (ref "IC37") (pin "21") (pinfunction "AGND_21") (pintype "passive"))
      (node (ref "IC37") (pin "3") (pinfunction "AGND_3") (pintype "passive"))
      (node (ref "IC37") (pin "9") (pinfunction "DGND_9") (pintype "passive"))
      (node (ref "IC38") (pin "5") (pinfunction "GND_5") (pintype "power_in"))
      (node (ref "J36") (pin "2") (pinfunction "Y_2") (pintype "passive"))
      (node (ref "J37") (pin "2") (pinfunction "Y_2") (pintype "passive"))
      (node (ref "J38") (pin "2") (pinfunction "Y_2") (pintype "passive"))
      (node (ref "R179") (pin "1") (pinfunction "1_1") (pintype "passive"))
      (node (ref "R195") (pin "1") (pinfunction "1_1") (pintype "passive"))
      (node (ref "R203") (pin "1") (pinfunction "1_1") (pintype "passive"))
      (node (ref "R204") (pin "2") (pinfunction "2_2") (pintype "passive"))
      (node (ref "R205") (pin "2") (pinfunction "2_2") (pintype "passive"))
      (node (ref "R206") (pin "2") (pinfunction "2_2") (pintype "passive"))
      (node (ref "R207") (pin "1") (pinfunction "1_1") (pintype "passive"))
      (node (ref "R213") (pin "2") (pinfunction "2_2") (pintype "passive"))
      (node (ref "XO1") (pin "2") (pinfunction "GND_2") (pintype "passive"))
      (node (ref "XO2") (pin "2") (pinfunction "GND_2") (pintype "passive"))
      (node (ref "XO3") (pin "2") (pinfunction "GND_2") (pintype "passive"))
      (node (ref "XO4") (pin "4") (pinfunction "GND_4") (pintype "passive"))
      (node (ref "XO5") (pin "2") (pinfunction "GND_2") (pintype "passive"))
    )
    (net (code "34") (name "Net-(C114-Pad2)") (class "Default")
      (node (ref "C114") (pin "2") (pinfunction "2_2") (pintype "passive"))
      (node (ref "C115") (pin "1") (pinfunction "1_1") (pintype "passive"))
      (node (ref "R179") (pin "2") (pinfunction "2_2") (pintype "passive"))
    )
    (net (code "35") (name "Net-(C115-Pad2)") (class "Default")
      (node (ref "C115") (pin "2") (pinfunction "2_2") (pintype "passive"))
      (node (ref "R175") (pin "1") (pinfunction "1_1") (pintype "passive"))
      (node (ref "R181") (pin "1") (pinfunction "1_1") (pintype "passive"))
      (node (ref "R184") (pin "2") (pinfunction "2_2") (pintype "passive"))
      (node (ref "R189") (pin "1") (pinfunction "1_1") (pintype "passive"))
    )
    (net (code "36") (name "Net-(C139-Pad2)") (class "Default")
      (node (ref "C139") (pin "2") (pinfunction "2_2") (pintype "passive"))
      (node (ref "C140") (pin "1") (pinfunction "1_1") (pintype "passive"))
      (node (ref "C141") (pin "1") (pinfunction "1_1") (pintype "passive"))
      (node (ref "FR7") (pin "2") (pinfunction "2_2") (pintype "passive"))
      (node (ref "IC37") (pin "6") (pinfunction "AVdd_6") (pintype "passive"))
      (node (ref "IC37") (pin "7") (pinfunction "AVdd_7") (pintype "passive"))
    )
    (net (code "37") (name "Net-(C142-Pad2)") (class "Default")
      (node (ref "C142") (pin "2") (pinfunction "2_2") (pintype "passive"))
      (node (ref "C143") (pin "1") (pinfunction "1_1") (pintype "passive"))
      (node (ref "R195") (pin "2") (pinfunction "2_2") (pintype "passive"))
    )
    (net (code "38") (name "Net-(C147-Pad2)") (class "Default")
      (node (ref "C147") (pin "2") (pinfunction "2_2") (pintype "passive"))
      (node (ref "R193") (pin "1") (pinfunction "1_1") (pintype "passive"))
      (node (ref "R194") (pin "2") (pinfunction "2_2") (pintype "passive"))
      (node (ref "R208") (pin "2") (pinfunction "2_2") (pintype "passive"))
      (node (ref "R210") (pin "1") (pinfunction "1_1") (pintype "passive"))
      (node (ref "R213") (pin "1") (pinfunction "1_1") (pintype "passive"))
      (node (ref "TP13") (pin "1") (pintype "passive"))
    )
    (net (code "39") (name "Net-(C154-Pad2)") (class "Default")
      (node (ref "C154") (pin "2") (pinfunction "2_2") (pintype "passive"))
      (node (ref "C155") (pin "1") (pinfunction "1_1") (pintype "passive"))
      (node (ref "R203") (pin "2") (pinfunction "2_2") (pintype "passive"))
    )
    (net (code "40") (name "Net-(C158-Pad2)") (class "Default")
      (node (ref "C158") (pin "2") (pinfunction "2_2") (pintype "passive"))
      (node (ref "R199") (pin "1") (pinfunction "1_1") (pintype "passive"))
      (node (ref "R201") (pin "2") (pinfunction "2_2") (pintype "passive"))
    )
    (net (code "41") (name "Net-(C159-Pad1)") (class "Default")
      (node (ref "C159") (pin "1") (pinfunction "1_1") (pintype "passive"))
      (node (ref "R207") (pin "2") (pinfunction "2_2") (pintype "passive"))
    )
    (net (code "42") (name "Net-(FR4-Pad2)") (class "Default")
      (node (ref "FR4") (pin "2") (pinfunction "2_2") (pintype "passive"))
      (node (ref "R176") (pin "1") (pinfunction "1_1") (pintype "passive"))
      (node (ref "R182") (pin "2") (pinfunction "2_2") (pintype "passive"))
      (node (ref "R183") (pin "1") (pinfunction "1_1") (pintype "passive"))
      (node (ref "R188") (pin "1") (pinfunction "1_1") (pintype "passive"))
    )
    (net (code "43") (name "Net-(IC31-CLKin)") (class "Default")
      (node (ref "C114") (pin "1") (pinfunction "1_1") (pintype "passive"))
      (node (ref "IC31") (pin "21") (pinfunction "CLKin_21") (pintype "passive"))
    )
    (net (code "44") (name "Net-(IC31-CLKin*)") (class "Default")
      (node (ref "C116") (pin "2") (pinfunction "2_2") (pintype "passive"))
      (node (ref "IC31") (pin "20") (pinfunction "CLKin*_20") (pintype "passive"))
    )
    (net (code "45") (name "Net-(IC31-OE)") (class "Default")
      (node (ref "IC31") (pin "24") (pinfunction "OE_24") (pintype "passive"))
      (node (ref "R177") (pin "1") (pinfunction "1_1") (pintype "passive"))
    )
    (net (code "46") (name "Net-(IC34-EN)") (class "Default")
      (node (ref "C134") (pin "2") (pinfunction "2_2") (pintype "passive"))
      (node (ref "C136") (pin "2") (pinfunction "2_2") (pintype "passive"))
      (node (ref "IC34") (pin "1") (pinfunction "IN_1") (pintype "input"))
      (node (ref "IC34") (pin "3") (pinfunction "EN_3") (pintype "input"))
      (node (ref "R188") (pin "2") (pinfunction "2_2") (pintype "passive"))
      (node (ref "R190") (pin "2") (pinfunction "2_2") (pintype "passive"))
    )
    (net (code "47") (name "Net-(IC34-OUT)") (class "Default")
      (node (ref "C135") (pin "2") (pinfunction "2_2") (pintype "passive"))
      (node (ref "C137") (pin "2") (pinfunction "2_2") (pintype "passive"))
      (node (ref "IC34") (pin "5") (pinfunction "OUT_5") (pintype "output"))
      (node (ref "R190") (pin "1") (pinfunction "1_1") (pintype "passive"))
      (node (ref "XO5") (pin "4") (pinfunction "VCC_4") (pintype "passive"))
    )
    (net (code "48") (name "Net-(IC36-Vdd)") (class "Default")
      (node (ref "C144") (pin "2") (pinfunction "2_2") (pintype "passive"))
      (node (ref "C145") (pin "1") (pinfunction "1_1") (pintype "passive"))
      (node (ref "C146") (pin "1") (pinfunction "1_1") (pintype "passive"))
      (node (ref "C163") (pin "1") (pinfunction "1_1") (pintype "passive"))
      (node (ref "FR8") (pin "1") (pinfunction "1_1") (pintype "passive"))
      (node (ref "IC36") (pin "1") (pinfunction "Vdd_1") (pintype "power_in"))
      (node (ref "IC38") (pin "4") (pinfunction "VDD_4") (pintype "power_in"))
      (node (ref "R198") (pin "2") (pinfunction "2_2") (pintype "passive"))
    )
    (net (code "49") (name "Net-(IC36-Vfb)") (class "Default")
      (node (ref "C152") (pin "1") (pinfunction "1_1") (pintype "passive"))
      (node (ref "IC36") (pin "3") (pinfunction "Vfb_3") (pintype "input"))
      (node (ref "IC36") (pin "4") (pinfunction "Vout_4") (pintype "output"))
      (node (ref "R193") (pin "2") (pinfunction "2_2") (pintype "passive"))
    )
    (net (code "50") (name "Net-(IC37-CE)") (class "Default")
      (node (ref "IC37") (pin "11") (pinfunction "CE_11") (pintype "passive"))
      (node (ref "R200") (pin "1") (pinfunction "1_1") (pintype "passive"))
    )
    (net (code "51") (name "Net-(IC37-CLK)") (class "Default")
      (node (ref "C162") (pin "1") (pinfunction "1_1") (pintype "passive"))
      (node (ref "IC37") (pin "12") (pinfunction "CLK_12") (pintype "passive"))
      (node (ref "R209") (pin "2") (pinfunction "2_2") (pintype "passive"))
    )
    (net (code "52") (name "Net-(IC37-CP)") (class "Default")
      (node (ref "C159") (pin "2") (pinfunction "2_2") (pintype "passive"))
      (node (ref "C160") (pin "2") (pinfunction "2_2") (pintype "passive"))
      (node (ref "IC37") (pin "20") (pinfunction "CP_20") (pintype "passive"))
      (node (ref "R201") (pin "1") (pinfunction "1_1") (pintype "passive"))
    )
    (net (code "53") (name "Net-(IC37-DATA)") (class "Default")
      (node (ref "IC37") (pin "13") (pinfunction "DATA_13") (pintype "passive"))
      (node (ref "R211") (pin "2") (pinfunction "2_2") (pintype "passive"))
    )
    (net (code "54") (name "Net-(IC37-LE)") (class "Default")
      (node (ref "IC37") (pin "14") (pinfunction "LE_14") (pintype "passive"))
      (node (ref "R212") (pin "2") (pinfunction "2_2") (pintype "passive"))
    )
    (net (code "55") (name "Net-(IC37-REFin)") (class "Default")
      (node (ref "C154") (pin "1") (pinfunction "1_1") (pintype "passive"))
      (node (ref "IC37") (pin "8") (pinfunction "REFin_8") (pintype "passive"))
    )
    (net (code "56") (name "Net-(IC37-RFinA)") (class "Default")
      (node (ref "C142") (pin "1") (pinfunction "1_1") (pintype "passive"))
      (node (ref "IC37") (pin "5") (pinfunction "RFinA_5") (pintype "passive"))
    )
    (net (code "57") (name "Net-(IC37-RFinB)") (class "Default")
      (node (ref "C161") (pin "1") (pinfunction "1_1") (pintype "passive"))
      (node (ref "IC37") (pin "4") (pinfunction "RFinB_4") (pintype "passive"))
    )
    (net (code "58") (name "Net-(IC37-Rset)") (class "Default")
      (node (ref "IC37") (pin "19") (pinfunction "Rset_19") (pintype "passive"))
      (node (ref "R206") (pin "1") (pinfunction "1_1") (pintype "passive"))
    )
    (net (code "59") (name "Net-(IC37-Vp)") (class "Default")
      (node (ref "C150") (pin "2") (pinfunction "2_2") (pintype "passive"))
      (node (ref "C153") (pin "1") (pinfunction "1_1") (pintype "passive"))
      (node (ref "IC37") (pin "18") (pinfunction "Vp_18") (pintype "passive"))
      (node (ref "R196") (pin "1") (pinfunction "1_1") (pintype "passive"))
    )
    (net (code "60") (name "Net-(IC38-VOUT)") (class "Default")
      (node (ref "IC38") (pin "6") (pinfunction "VOUT_6") (pintype "tri_state"))
      (node (ref "R210") (pin "2") (pinfunction "2_2") (pintype "passive"))
    )
    (net (code "61") (name "Net-(J37-X)") (class "Default")
      (node (ref "J37") (pin "1") (pinfunction "X_1") (pintype "passive"))
      (node (ref "R178") (pin "1") (pinfunction "1_1") (pintype "passive"))
    )
    (net (code "62") (name "Net-(R183-Pad2)") (class "Default")
      (node (ref "R183") (pin "2") (pinfunction "2_2") (pintype "passive"))
      (node (ref "R185") (pin "1") (pinfunction "1_1") (pintype "passive"))
    )
    (net (code "63") (name "Net-(XO1-Output)") (class "Default")
      (node (ref "R175") (pin "2") (pinfunction "2_2") (pintype "passive"))
      (node (ref "XO1") (pin "3") (pinfunction "Output_3") (pintype "output"))
    )
    (net (code "64") (name "Net-(XO1-Vcc)") (class "Default")
      (node (ref "C111") (pin "2") (pinfunction "2_2") (pintype "passive"))
      (node (ref "C112") (pin "2") (pinfunction "2_2") (pintype "passive"))
      (node (ref "C113") (pin "1") (pinfunction "1_1") (pintype "passive"))
      (node (ref "R176") (pin "2") (pinfunction "2_2") (pintype "passive"))
      (node (ref "XO1") (pin "4") (pinfunction "Vcc_4") (pintype "power_in"))
    )
    (net (code "65") (name "Net-(XO2-OUT)") (class "Default")
      (node (ref "R181") (pin "2") (pinfunction "2_2") (pintype "passive"))
      (node (ref "XO2") (pin "4") (pinfunction "OUT_4") (pintype "passive"))
      (node (ref "XO3") (pin "3") (pinfunction "OUT_3") (pintype "passive"))
    )
    (net (code "66") (name "Net-(XO2-TRI-ST.)") (class "Default")
      (node (ref "R180") (pin "1") (pinfunction "1_1") (pintype "passive"))
      (node (ref "XO2") (pin "6") (pinfunction "TRI-ST._6") (pintype "passive"))
    )
    (net (code "67") (name "Net-(XO2-VDD)") (class "Default")
      (node (ref "C118") (pin "2") (pinfunction "2_2") (pintype "passive"))
      (node (ref "C119") (pin "2") (pinfunction "2_2") (pintype "passive"))
      (node (ref "R180") (pin "2") (pinfunction "2_2") (pintype "passive"))
      (node (ref "R182") (pin "1") (pinfunction "1_1") (pintype "passive"))
      (node (ref "XO2") (pin "5") (pinfunction "VDD_5") (pintype "passive"))
      (node (ref "XO3") (pin "4") (pinfunction "VDD_4") (pintype "passive"))
    )
    (net (code "68") (name "Net-(XO4-RF_OUT)") (class "Default")
      (node (ref "R184") (pin "1") (pinfunction "1_1") (pintype "passive"))
      (node (ref "XO4") (pin "6") (pinfunction "RF_OUT_6") (pintype "output"))
    )
    (net (code "69") (name "Net-(XO4-VCC)") (class "Default")
      (node (ref "C124") (pin "2") (pinfunction "2_2") (pintype "passive"))
      (node (ref "C125") (pin "2") (pinfunction "2_2") (pintype "passive"))
      (node (ref "R185") (pin "2") (pinfunction "2_2") (pintype "passive"))
      (node (ref "XO4") (pin "9") (pinfunction "VCC_9") (pintype "power_in"))
    )
    (net (code "70") (name "Net-(XO4-VC_FILTER)") (class "Default")
      (node (ref "C126") (pin "2") (pinfunction "2_2") (pintype "passive"))
      (node (ref "XO4") (pin "7") (pinfunction "VC_FILTER_7") (pintype "input"))
    )
    (net (code "71") (name "Net-(XO5-OUT)") (class "Default")
      (node (ref "R189") (pin "2") (pinfunction "2_2") (pintype "passive"))
      (node (ref "R191") (pin "1") (pinfunction "1_1") (pintype "passive"))
      (node (ref "XO5") (pin "3") (pinfunction "OUT_3") (pintype "passive"))
    )
    (net (code "72") (name "VCC2P5") (class "Default")
      (node (ref "R202") (pin "2") (pinfunction "2_2") (pintype "passive"))
    )
    (net (code "73") (name "VCC2P5_VREF") (class "Default")
      (node (ref "R197") (pin "2") (pinfunction "2_2") (pintype "passive"))
    )
    (net (code "74") (name "VCC3P3_CLK") (class "Default")
      (node (ref "C117") (pin "2") (pinfunction "2_2") (pintype "passive"))
      (node (ref "C133") (pin "2") (pinfunction "2_2") (pintype "passive"))
      (node (ref "C138") (pin "2") (pinfunction "2_2") (pintype "passive"))
      (node (ref "C148") (pin "1") (pinfunction "1_1") (pintype "passive"))
      (node (ref "C149") (pin "1") (pinfunction "1_1") (pintype "passive"))
      (node (ref "C151") (pin "2") (pinfunction "2_2") (pintype "passive"))
      (node (ref "FR4") (pin "1") (pinfunction "1_1") (pintype "passive"))
      (node (ref "FR5") (pin "1") (pinfunction "1_1") (pintype "passive"))
      (node (ref "FR6") (pin "1") (pinfunction "1_1") (pintype "passive"))
      (node (ref "FR7") (pin "1") (pinfunction "1_1") (pintype "passive"))
      (node (ref "FR8") (pin "2") (pinfunction "2_2") (pintype "passive"))
      (node (ref "IC32") (pin "6") (pinfunction "VDD_6") (pintype "power_in"))
      (node (ref "IC33") (pin "5") (pinfunction "VCC_5") (pintype "passive"))
      (node (ref "IC35") (pin "5") (pinfunction "VCC_5") (pintype "passive"))
      (node (ref "IC37") (pin "16") (pinfunction "DVdd_16") (pintype "passive"))
      (node (ref "IC37") (pin "17") (pinfunction "DVdd_17") (pintype "passive"))
      (node (ref "R196") (pin "2") (pinfunction "2_2") (pintype "passive"))
      (node (ref "R200") (pin "2") (pinfunction "2_2") (pintype "passive"))
      (node (ref "R208") (pin "1") (pinfunction "1_1") (pintype "passive"))
    )
    (net (code "75") (name "VCC3P3_LMKRF") (class "Default")
      (node (ref "C120") (pin "2") (pinfunction "2_2") (pintype "passive"))
      (node (ref "C121") (pin "2") (pinfunction "2_2") (pintype "passive"))
      (node (ref "C122") (pin "2") (pinfunction "2_2") (pintype "passive"))
      (node (ref "C123") (pin "2") (pinfunction "2_2") (pintype "passive"))
      (node (ref "FR5") (pin "2") (pinfunction "2_2") (pintype "passive"))
      (node (ref "IC31") (pin "23") (pinfunction "Vdd_23") (pintype "passive"))
      (node (ref "IC31") (pin "8") (pinfunction "Vdd_8") (pintype "passive"))
      (node (ref "R177") (pin "2") (pinfunction "2_2") (pintype "passive"))
    )
    (net (code "76") (name "VCC3P3_LMKRF_VDDO") (class "Default")
      (node (ref "C127") (pin "2") (pinfunction "2_2") (pintype "passive"))
      (node (ref "C128") (pin "2") (pinfunction "2_2") (pintype "passive"))
      (node (ref "C129") (pin "2") (pinfunction "2_2") (pintype "passive"))
      (node (ref "C130") (pin "2") (pinfunction "2_2") (pintype "passive"))
      (node (ref "C131") (pin "2") (pinfunction "2_2") (pintype "passive"))
      (node (ref "C132") (pin "2") (pinfunction "2_2") (pintype "passive"))
      (node (ref "FR6") (pin "2") (pinfunction "2_2") (pintype "passive"))
      (node (ref "IC31") (pin "14") (pinfunction "Vddo_14") (pintype "passive"))
      (node (ref "IC31") (pin "18") (pinfunction "Vddo_18") (pintype "passive"))
      (node (ref "IC31") (pin "2") (pinfunction "Vddo_2") (pintype "passive"))
      (node (ref "IC31") (pin "6") (pinfunction "Vddo_6") (pintype "passive"))
    )
    (net (code "77") (name "unconnected-(IC31-OSCin-Pad9)") (class "Default")
      (node (ref "IC31") (pin "9") (pinfunction "OSCin_9") (pintype "passive+no_connect"))
    )
    (net (code "78") (name "unconnected-(IC31-OSCout-Pad10)") (class "Default")
      (node (ref "IC31") (pin "10") (pinfunction "OSCout_10") (pintype "passive+no_connect"))
    )
    (net (code "79") (name "unconnected-(IC34-NC-Pad4)") (class "Default")
      (node (ref "IC34") (pin "4") (pinfunction "NC_4") (pintype "passive+no_connect"))
    )
    (net (code "80") (name "unconnected-(XO2-T.S.-Pad3)") (class "Default")
      (node (ref "XO2") (pin "3") (pinfunction "T.S._3") (pintype "passive+no_connect"))
    )
    (net (code "81") (name "unconnected-(XO4-NC-Pad2)") (class "Default")
      (node (ref "XO4") (pin "2") (pinfunction "NC_2") (pintype "passive+no_connect"))
    )
    (net (code "82") (name "unconnected-(XO4-NC-Pad3)") (class "Default")
      (node (ref "XO4") (pin "3") (pinfunction "NC_3") (pintype "passive+no_connect"))
    )
    (net (code "83") (name "unconnected-(XO4-NC-Pad5)") (class "Default")
      (node (ref "XO4") (pin "5") (pinfunction "NC_5") (pintype "passive+no_connect"))
    )
    (net (code "84") (name "unconnected-(XO4-NC-Pad8)") (class "Default")
      (node (ref "XO4") (pin "8") (pinfunction "NC_8") (pintype "passive+no_connect"))
    )
    (net (code "85") (name "unconnected-(XO4-NC-Pad10)") (class "Default")
      (node (ref "XO4") (pin "10") (pinfunction "NC_10") (pintype "passive+no_connect"))
    )
  )
)
